# QAn_Smar_Shield_1_0.net
KiCad netlist of a schematic drawn in EAGLE
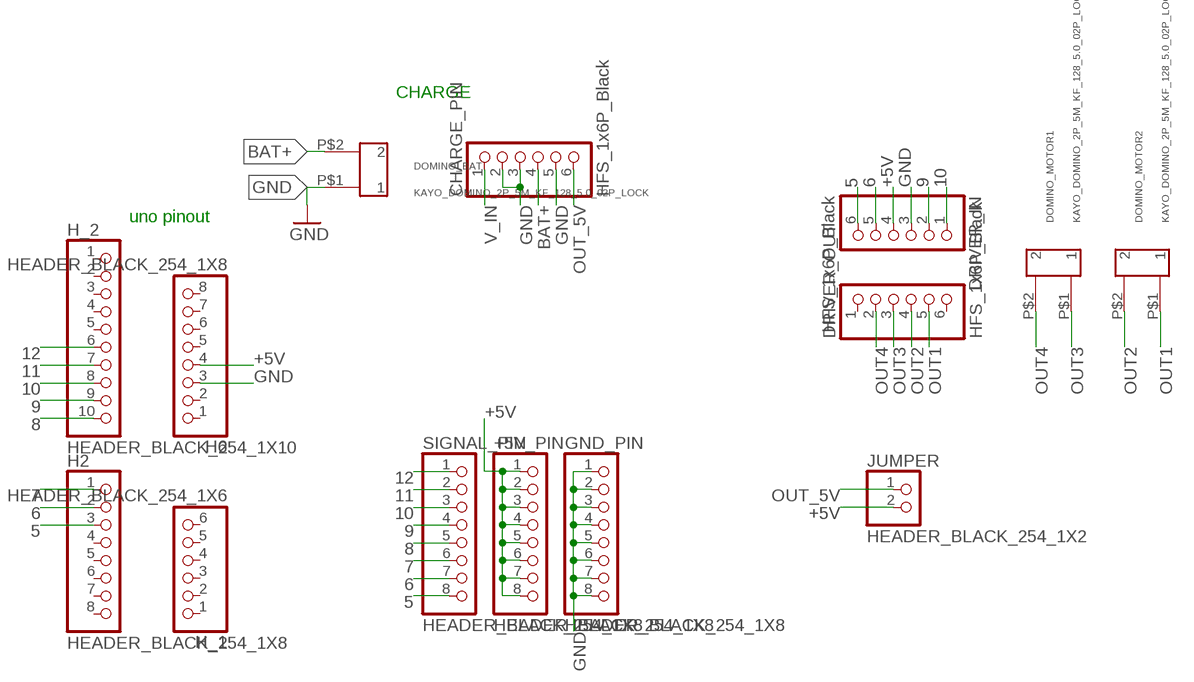
[diagram p0: schematic, sheet 1]
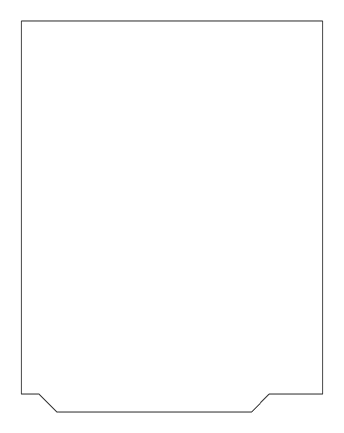
[diagram p1: schematic, sheet 2]
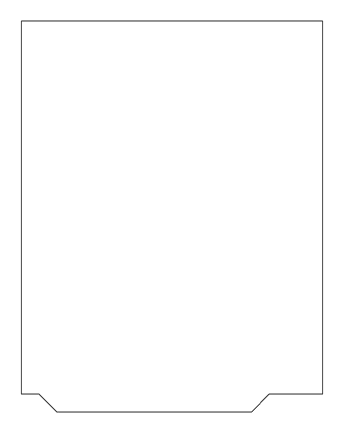
[diagram p2: schematic, sheet 3]

(export (version "E")
  (design (tool "Eeschema 10.0.6"))
  (components
    (comp (ref "+5V_PIN")
      (value "HEADER_BLACK_254_1X8")
      (footprint "eagle-import:HEADER_1X8_254_LOCK")
      (libsource (lib "eagle-import") (part "KXN_HEADER_1X8_M_LOCK"))
    )
    (comp (ref "CHARGE_PIN")
      (value "HFS_1x6P_Black")
      (footprint "eagle-import:HEADER_1X6_LOCK_FEMALE")
      (libsource (lib "eagle-import") (part "KXN_HEADER_1X6_LF"))
    )
    (comp (ref "DOMINO_BAT")
      (value "KAYO_DOMINO_2P_5M_KF_128_5.0_02P_LOCK")
      (footprint "eagle-import:KF128-5.0-02P")
      (libsource (lib "eagle-import") (part "KAYO_DOMINO_2P_5M_KF_128_5.0_02P_LOCK"))
    )
    (comp (ref "DOMINO_MOTOR1")
      (value "KAYO_DOMINO_2P_5M_KF_128_5.0_02P_LOCK")
      (footprint "eagle-import:KF128-5.0-02P")
      (libsource (lib "eagle-import") (part "KAYO_DOMINO_2P_5M_KF_128_5.0_02P_LOCK"))
    )
    (comp (ref "DOMINO_MOTOR2")
      (value "KAYO_DOMINO_2P_5M_KF_128_5.0_02P_LOCK")
      (footprint "eagle-import:KF128-5.0-02P")
      (libsource (lib "eagle-import") (part "KAYO_DOMINO_2P_5M_KF_128_5.0_02P_LOCK"))
    )
    (comp (ref "DRIVER_IN")
      (value "HFS_1x6P_Black")
      (footprint "eagle-import:HEADER_1X6_LOCK_FEMALE")
      (libsource (lib "eagle-import") (part "KXN_HEADER_1X6_LF"))
    )
    (comp (ref "DRIVER_OUT")
      (value "HFS_1x6P_Black")
      (footprint "eagle-import:HEADER_1X6_LOCK_FEMALE")
      (libsource (lib "eagle-import") (part "KXN_HEADER_1X6_LF"))
    )
    (comp (ref "GND_PIN")
      (value "HEADER_BLACK_254_1X8")
      (footprint "eagle-import:HEADER_1X8_254_LOCK")
      (libsource (lib "eagle-import") (part "KXN_HEADER_1X8_M_LOCK"))
    )
    (comp (ref "H2")
      (value "HEADER_BLACK_254_1X8")
      (footprint "eagle-import:HEADER_1X8_254_LOCK")
      (libsource (lib "eagle-import") (part "KXN_HEADER_1X8_M_LOCK"))
    )
    (comp (ref "H6")
      (value "HEADER_BLACK_254_1X8")
      (footprint "eagle-import:HEADER_1X8_254_LOCK")
      (libsource (lib "eagle-import") (part "KXN_HEADER_1X8_M_LOCK"))
    )
    (comp (ref "H_1")
      (value "HEADER_BLACK_254_1X6")
      (footprint "eagle-import:HEADER_1X6_254_LOCK")
      (libsource (lib "eagle-import") (part "KXN_HEADER_1X6_M_LOCK"))
    )
    (comp (ref "H_2")
      (value "HEADER_BLACK_254_1X10")
      (footprint "eagle-import:HEADER_1X10_254_LOCK")
      (libsource (lib "eagle-import") (part "KXN_HEADER_1X10_M_LOCK"))
    )
    (comp (ref "JUMPER")
      (value "HEADER_BLACK_254_1X2")
      (footprint "eagle-import:HEADER_1X2_254_LOCK")
      (libsource (lib "eagle-import") (part "KXN_HEADER_1X2_LOCK"))
    )
    (comp (ref "SIGNAL_PIN")
      (value "HEADER_BLACK_254_1X8")
      (footprint "eagle-import:HEADER_1X8_254_LOCK")
      (libsource (lib "eagle-import") (part "KXN_HEADER_1X8_M_LOCK"))
    )
  )
  (nets
    (net (code "1") (name "+5V") (class "Default")
      (node (ref "+5V_PIN") (pin "1") (pinfunction "1_1") (pintype "passive"))
      (node (ref "+5V_PIN") (pin "2") (pinfunction "2_2") (pintype "passive"))
      (node (ref "+5V_PIN") (pin "3") (pinfunction "3_3") (pintype "passive"))
      (node (ref "+5V_PIN") (pin "4") (pinfunction "4_4") (pintype "passive"))
      (node (ref "+5V_PIN") (pin "5") (pinfunction "5_5") (pintype "passive"))
      (node (ref "+5V_PIN") (pin "6") (pinfunction "6_6") (pintype "passive"))
      (node (ref "+5V_PIN") (pin "7") (pinfunction "7_7") (pintype "passive"))
      (node (ref "+5V_PIN") (pin "8") (pinfunction "8_8") (pintype "passive"))
      (node (ref "DRIVER_IN") (pin "4") (pinfunction "4_4") (pintype "passive"))
      (node (ref "H6") (pin "4") (pinfunction "4_4") (pintype "passive"))
      (node (ref "JUMPER") (pin "2") (pinfunction "2_2") (pintype "passive"))
    )
    (net (code "2") (name "5") (class "Default")
      (node (ref "DRIVER_IN") (pin "6") (pinfunction "6_6") (pintype "passive"))
      (node (ref "H2") (pin "3") (pinfunction "3_3") (pintype "passive"))
      (node (ref "SIGNAL_PIN") (pin "8") (pinfunction "8_8") (pintype "passive"))
    )
    (net (code "3") (name "6") (class "Default")
      (node (ref "DRIVER_IN") (pin "5") (pinfunction "5_5") (pintype "passive"))
      (node (ref "H2") (pin "2") (pinfunction "2_2") (pintype "passive"))
      (node (ref "SIGNAL_PIN") (pin "7") (pinfunction "7_7") (pintype "passive"))
    )
    (net (code "4") (name "7") (class "Default")
      (node (ref "H2") (pin "1") (pinfunction "1_1") (pintype "passive"))
      (node (ref "SIGNAL_PIN") (pin "6") (pinfunction "6_6") (pintype "passive"))
    )
    (net (code "5") (name "8") (class "Default")
      (node (ref "H_2") (pin "10") (pinfunction "10_10") (pintype "passive"))
      (node (ref "SIGNAL_PIN") (pin "5") (pinfunction "5_5") (pintype "passive"))
    )
    (net (code "6") (name "9") (class "Default")
      (node (ref "DRIVER_IN") (pin "2") (pinfunction "2_2") (pintype "passive"))
      (node (ref "H_2") (pin "9") (pinfunction "9_9") (pintype "passive"))
      (node (ref "SIGNAL_PIN") (pin "4") (pinfunction "4_4") (pintype "passive"))
    )
    (net (code "7") (name "10") (class "Default")
      (node (ref "DRIVER_IN") (pin "1") (pinfunction "1_1") (pintype "passive"))
      (node (ref "H_2") (pin "8") (pinfunction "8_8") (pintype "passive"))
      (node (ref "SIGNAL_PIN") (pin "3") (pinfunction "3_3") (pintype "passive"))
    )
    (net (code "8") (name "11") (class "Default")
      (node (ref "H_2") (pin "7") (pinfunction "7_7") (pintype "passive"))
      (node (ref "SIGNAL_PIN") (pin "2") (pinfunction "2_2") (pintype "passive"))
    )
    (net (code "9") (name "12") (class "Default")
      (node (ref "H_2") (pin "6") (pinfunction "6_6") (pintype "passive"))
      (node (ref "SIGNAL_PIN") (pin "1") (pinfunction "1_1") (pintype "passive"))
    )
    (net (code "10") (name "BAT+") (class "Default")
      (node (ref "CHARGE_PIN") (pin "4") (pinfunction "4_4") (pintype "passive"))
      (node (ref "DOMINO_BAT") (pin "P$2") (pinfunction "2_P$2") (pintype "bidirectional"))
    )
    (net (code "11") (name "GND") (class "Default")
      (node (ref "CHARGE_PIN") (pin "2") (pinfunction "2_2") (pintype "passive"))
      (node (ref "CHARGE_PIN") (pin "3") (pinfunction "3_3") (pintype "passive"))
      (node (ref "CHARGE_PIN") (pin "5") (pinfunction "5_5") (pintype "passive"))
      (node (ref "DOMINO_BAT") (pin "P$1") (pinfunction "1_P$1") (pintype "bidirectional"))
      (node (ref "DRIVER_IN") (pin "3") (pinfunction "3_3") (pintype "passive"))
      (node (ref "GND_PIN") (pin "1") (pinfunction "1_1") (pintype "passive"))
      (node (ref "GND_PIN") (pin "2") (pinfunction "2_2") (pintype "passive"))
      (node (ref "GND_PIN") (pin "3") (pinfunction "3_3") (pintype "passive"))
      (node (ref "GND_PIN") (pin "4") (pinfunction "4_4") (pintype "passive"))
      (node (ref "GND_PIN") (pin "5") (pinfunction "5_5") (pintype "passive"))
      (node (ref "GND_PIN") (pin "6") (pinfunction "6_6") (pintype "passive"))
      (node (ref "GND_PIN") (pin "7") (pinfunction "7_7") (pintype "passive"))
      (node (ref "GND_PIN") (pin "8") (pinfunction "8_8") (pintype "passive"))
      (node (ref "H6") (pin "3") (pinfunction "3_3") (pintype "passive"))
    )
    (net (code "12") (name "OUT1") (class "Default")
      (node (ref "DOMINO_MOTOR2") (pin "P$1") (pinfunction "1_P$1") (pintype "bidirectional"))
      (node (ref "DRIVER_OUT") (pin "5") (pinfunction "5_5") (pintype "passive"))
    )
    (net (code "13") (name "OUT2") (class "Default")
      (node (ref "DOMINO_MOTOR2") (pin "P$2") (pinfunction "2_P$2") (pintype "bidirectional"))
      (node (ref "DRIVER_OUT") (pin "4") (pinfunction "4_4") (pintype "passive"))
    )
    (net (code "14") (name "OUT3") (class "Default")
      (node (ref "DOMINO_MOTOR1") (pin "P$1") (pinfunction "1_P$1") (pintype "bidirectional"))
      (node (ref "DRIVER_OUT") (pin "3") (pinfunction "3_3") (pintype "passive"))
    )
    (net (code "15") (name "OUT4") (class "Default")
      (node (ref "DOMINO_MOTOR1") (pin "P$2") (pinfunction "2_P$2") (pintype "bidirectional"))
      (node (ref "DRIVER_OUT") (pin "2") (pinfunction "2_2") (pintype "passive"))
    )
    (net (code "16") (name "OUT_5V") (class "Default")
      (node (ref "CHARGE_PIN") (pin "6") (pinfunction "6_6") (pintype "passive"))
      (node (ref "JUMPER") (pin "1") (pinfunction "1_1") (pintype "passive"))
    )
    (net (code "17") (name "V_IN") (class "Default")
      (node (ref "CHARGE_PIN") (pin "1") (pinfunction "1_1") (pintype "passive"))
    )
    (net (code "18") (name "unconnected-(DRIVER_OUT-Pad1)") (class "Default")
      (node (ref "DRIVER_OUT") (pin "1") (pinfunction "1_1") (pintype "passive"))
    )
    (net (code "19") (name "unconnected-(DRIVER_OUT-Pad6)") (class "Default")
      (node (ref "DRIVER_OUT") (pin "6") (pinfunction "6_6") (pintype "passive"))
    )
    (net (code "20") (name "unconnected-(H2-Pad4)") (class "Default")
      (node (ref "H2") (pin "4") (pinfunction "4_4") (pintype "passive"))
    )
    (net (code "21") (name "unconnected-(H2-Pad5)") (class "Default")
      (node (ref "H2") (pin "5") (pinfunction "5_5") (pintype "passive"))
    )
    (net (code "22") (name "unconnected-(H2-Pad6)") (class "Default")
      (node (ref "H2") (pin "6") (pinfunction "6_6") (pintype "passive"))
    )
    (net (code "23") (name "unconnected-(H2-Pad7)") (class "Default")
      (node (ref "H2") (pin "7") (pinfunction "7_7") (pintype "passive"))
    )
    (net (code "24") (name "unconnected-(H2-Pad8)") (class "Default")
      (node (ref "H2") (pin "8") (pinfunction "8_8") (pintype "passive"))
    )
    (net (code "25") (name "unconnected-(H6-Pad1)") (class "Default")
      (node (ref "H6") (pin "1") (pinfunction "1_1") (pintype "passive"))
    )
    (net (code "26") (name "unconnected-(H6-Pad2)") (class "Default")
      (node (ref "H6") (pin "2") (pinfunction "2_2") (pintype "passive"))
    )
    (net (code "27") (name "unconnected-(H6-Pad5)") (class "Default")
      (node (ref "H6") (pin "5") (pinfunction "5_5") (pintype "passive"))
    )
    (net (code "28") (name "unconnected-(H6-Pad6)") (class "Default")
      (node (ref "H6") (pin "6") (pinfunction "6_6") (pintype "passive"))
    )
    (net (code "29") (name "unconnected-(H6-Pad7)") (class "Default")
      (node (ref "H6") (pin "7") (pinfunction "7_7") (pintype "passive"))
    )
    (net (code "30") (name "unconnected-(H6-Pad8)") (class "Default")
      (node (ref "H6") (pin "8") (pinfunction "8_8") (pintype "passive"))
    )
    (net (code "31") (name "unconnected-(H_1-Pad1)") (class "Default")
      (node (ref "H_1") (pin "1") (pinfunction "1_1") (pintype "passive"))
    )
    (net (code "32") (name "unconnected-(H_1-Pad2)") (class "Default")
      (node (ref "H_1") (pin "2") (pinfunction "2_2") (pintype "passive"))
    )
    (net (code "33") (name "unconnected-(H_1-Pad3)") (class "Default")
      (node (ref "H_1") (pin "3") (pinfunction "3_3") (pintype "passive"))
    )
    (net (code "34") (name "unconnected-(H_1-Pad4)") (class "Default")
      (node (ref "H_1") (pin "4") (pinfunction "4_4") (pintype "passive"))
    )
    (net (code "35") (name "unconnected-(H_1-Pad5)") (class "Default")
      (node (ref "H_1") (pin "5") (pinfunction "5_5") (pintype "passive"))
    )
    (net (code "36") (name "unconnected-(H_1-Pad6)") (class "Default")
      (node (ref "H_1") (pin "6") (pinfunction "6_6") (pintype "passive"))
    )
    (net (code "37") (name "unconnected-(H_2-Pad1)") (class "Default")
      (node (ref "H_2") (pin "1") (pinfunction "1_1") (pintype "passive"))
    )
    (net (code "38") (name "unconnected-(H_2-Pad2)") (class "Default")
      (node (ref "H_2") (pin "2") (pinfunction "2_2") (pintype "passive"))
    )
    (net (code "39") (name "unconnected-(H_2-Pad3)") (class "Default")
      (node (ref "H_2") (pin "3") (pinfunction "3_3") (pintype "passive"))
    )
    (net (code "40") (name "unconnected-(H_2-Pad4)") (class "Default")
      (node (ref "H_2") (pin "4") (pinfunction "4_4") (pintype "passive"))
    )
    (net (code "41") (name "unconnected-(H_2-Pad5)") (class "Default")
      (node (ref "H_2") (pin "5") (pinfunction "5_5") (pintype "passive"))
    )
  )
)
